# 3_MCU.net
KiCad netlist of a schematic drawn in Altium Designer
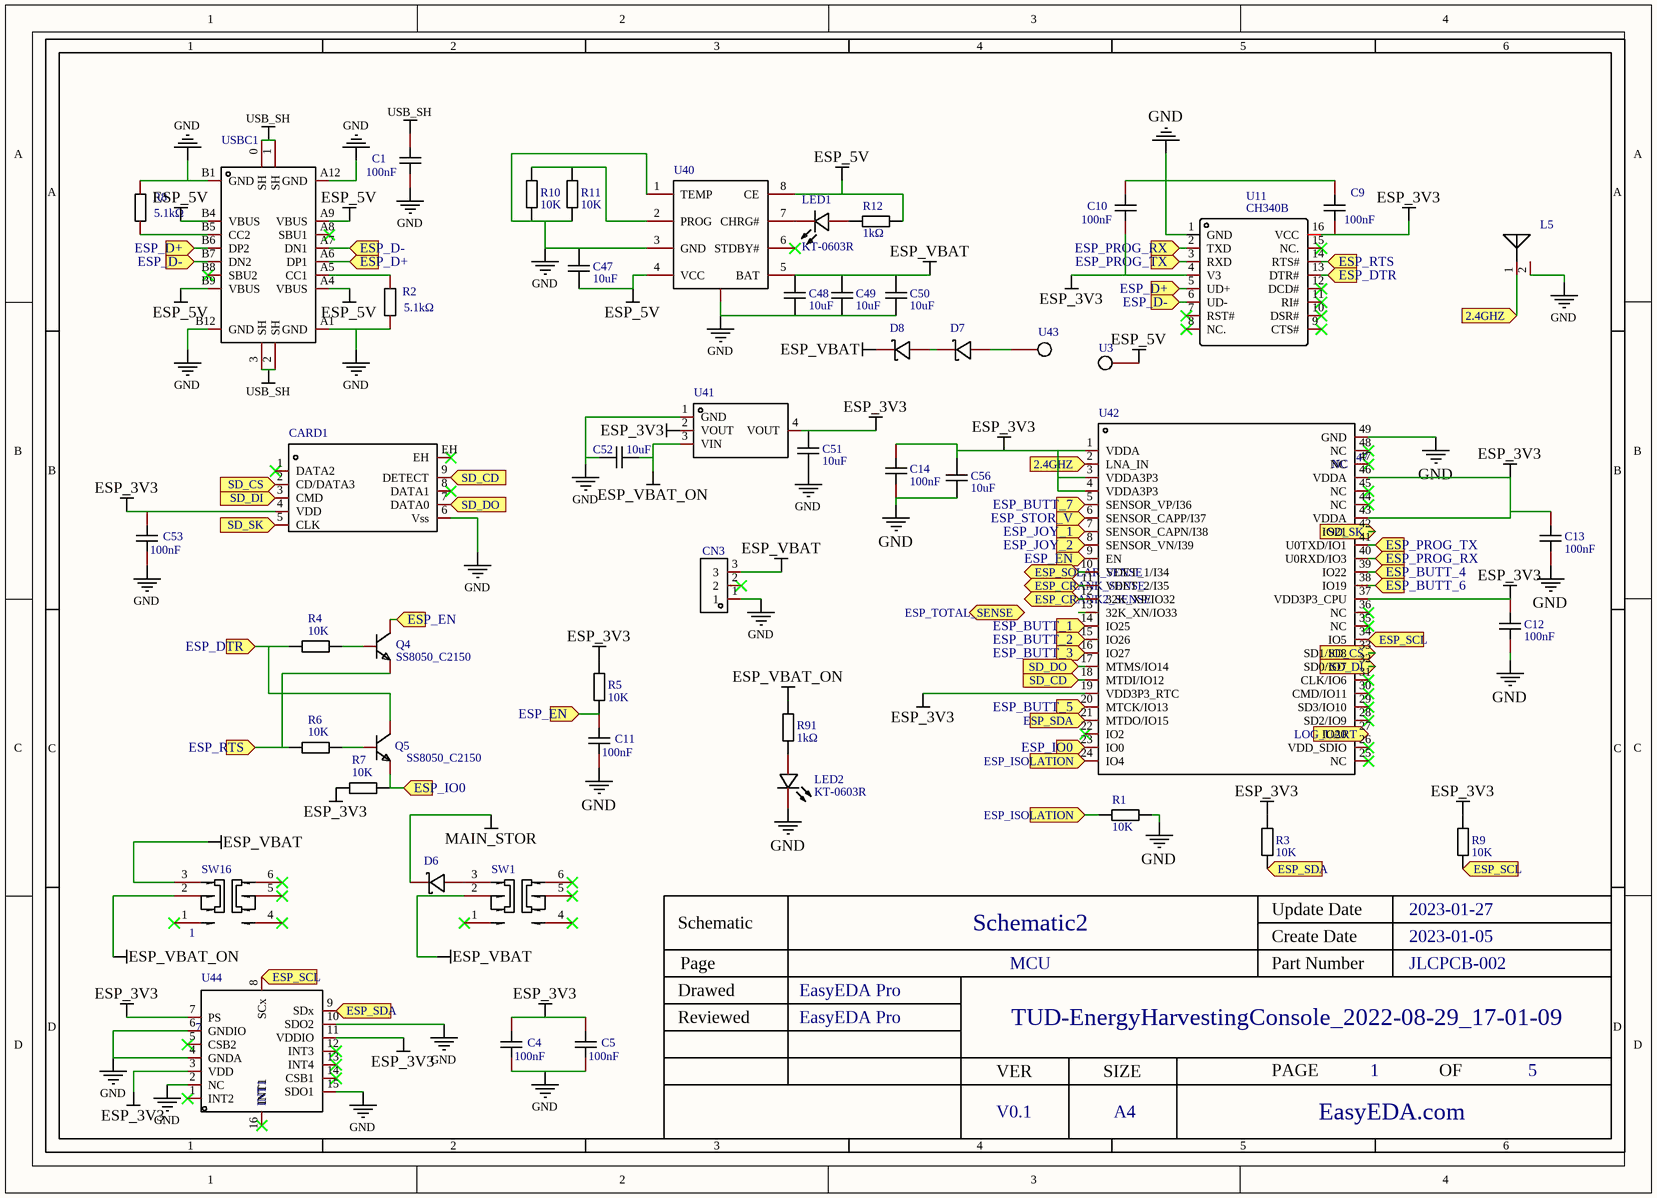
[diagram p0: 3_MCU.schdoc]

(export (version "E")
  (design (tool "Eeschema 10.0.6"))
  (components
    (comp (ref "C1")
      (value "100nF")
      (fields
        (field (name "NAME") "100nF")
        (field (name "MANUFACTURER") "YAGEO")
        (field (name "MANUFACTURER PART") "CC0603KRX7R9BB104")
      )
      (libsource (lib "altium-import") (part "root_1_CC0603KRX7R9BB104_"))
    )
    (comp (ref "C4")
      (value "100nF")
      (fields
        (field (name "NAME") "100nF")
        (field (name "MANUFACTURER") "YAGEO")
        (field (name "MANUFACTURER PART") "CC0603KRX7R9BB104")
      )
      (libsource (lib "altium-import") (part "root_1_CC0603KRX7R9BB104_"))
    )
    (comp (ref "C5")
      (value "100nF")
      (fields
        (field (name "NAME") "100nF")
        (field (name "MANUFACTURER") "YAGEO")
        (field (name "MANUFACTURER PART") "CC0603KRX7R9BB104")
      )
      (libsource (lib "altium-import") (part "root_1_CC0603KRX7R9BB104_"))
    )
    (comp (ref "C9")
      (value "100nF")
      (fields
        (field (name "NAME") "100nF")
        (field (name "MANUFACTURER") "YAGEO")
        (field (name "MANUFACTURER PART") "CC0603KRX7R9BB104")
      )
      (libsource (lib "altium-import") (part "root_1_CC0603KRX7R9BB104_"))
    )
    (comp (ref "C10")
      (value "100nF")
      (fields
        (field (name "NAME") "100nF")
        (field (name "MANUFACTURER") "YAGEO")
        (field (name "MANUFACTURER PART") "CC0603KRX7R9BB104")
      )
      (libsource (lib "altium-import") (part "root_1_CC0603KRX7R9BB104_"))
    )
    (comp (ref "C11")
      (value "100nF")
      (fields
        (field (name "NAME") "100nF")
        (field (name "MANUFACTURER") "YAGEO")
        (field (name "MANUFACTURER PART") "CC0603KRX7R9BB104")
      )
      (libsource (lib "altium-import") (part "root_1_CC0603KRX7R9BB104_"))
    )
    (comp (ref "C12")
      (value "100nF")
      (fields
        (field (name "NAME") "100nF")
        (field (name "MANUFACTURER PART") "CL05B104KO5NNNC")
        (field (name "MANUFACTURER") "SAMSUNG")
      )
      (libsource (lib "altium-import") (part "root_1_CL05B104KO5NNNC_"))
    )
    (comp (ref "C13")
      (value "100nF")
      (fields
        (field (name "NAME") "100nF")
        (field (name "MANUFACTURER PART") "CL05B104KO5NNNC")
        (field (name "MANUFACTURER") "SAMSUNG")
      )
      (libsource (lib "altium-import") (part "root_1_CL05B104KO5NNNC_"))
    )
    (comp (ref "C14")
      (value "100nF")
      (fields
        (field (name "NAME") "100nF")
        (field (name "MANUFACTURER PART") "CL05B104KO5NNNC")
        (field (name "MANUFACTURER") "SAMSUNG")
      )
      (libsource (lib "altium-import") (part "root_1_CL05B104KO5NNNC_"))
    )
    (comp (ref "C47")
      (value "10uF")
      (fields
        (field (name "NAME") "10uF")
        (field (name "MANUFACTURER PART") "CL05A106MQ5NUNC")
        (field (name "MANUFACTURER") "SAMSUNG")
      )
      (libsource (lib "altium-import") (part "root_3_CL05A106MQ5NUNC_"))
    )
    (comp (ref "C48")
      (value "10uF")
      (fields
        (field (name "NAME") "10uF")
        (field (name "MANUFACTURER PART") "CL05A106MQ5NUNC")
        (field (name "MANUFACTURER") "SAMSUNG")
      )
      (libsource (lib "altium-import") (part "root_3_CL05A106MQ5NUNC_"))
    )
    (comp (ref "C49")
      (value "10uF")
      (fields
        (field (name "NAME") "10uF")
        (field (name "MANUFACTURER PART") "CL05A106MQ5NUNC")
        (field (name "MANUFACTURER") "SAMSUNG")
      )
      (libsource (lib "altium-import") (part "root_3_CL05A106MQ5NUNC_"))
    )
    (comp (ref "C50")
      (value "10uF")
      (fields
        (field (name "NAME") "10uF")
        (field (name "MANUFACTURER PART") "CL05A106MQ5NUNC")
        (field (name "MANUFACTURER") "SAMSUNG")
      )
      (libsource (lib "altium-import") (part "root_3_CL05A106MQ5NUNC_"))
    )
    (comp (ref "C51")
      (value "10uF")
      (fields
        (field (name "NAME") "10uF")
        (field (name "MANUFACTURER PART") "CL05A106MQ5NUNC")
        (field (name "MANUFACTURER") "SAMSUNG")
      )
      (libsource (lib "altium-import") (part "root_3_CL05A106MQ5NUNC_"))
    )
    (comp (ref "C52")
      (value "10uF")
      (fields
        (field (name "NAME") "10uF")
        (field (name "MANUFACTURER PART") "CL05A106MQ5NUNC")
        (field (name "MANUFACTURER") "SAMSUNG")
      )
      (libsource (lib "altium-import") (part "root_0_CL05A106MQ5NUNC_"))
    )
    (comp (ref "C53")
      (value "100nF")
      (fields
        (field (name "NAME") "100nF")
        (field (name "MANUFACTURER") "YAGEO")
        (field (name "MANUFACTURER PART") "CC0603KRX7R9BB104")
      )
      (libsource (lib "altium-import") (part "root_1_CC0603KRX7R9BB104_"))
    )
    (comp (ref "C56")
      (value "10uF")
      (fields
        (field (name "NAME") "10uF")
        (field (name "MANUFACTURER PART") "CL05A106MQ5NUNC")
        (field (name "MANUFACTURER") "SAMSUNG")
      )
      (libsource (lib "altium-import") (part "root_3_CL05A106MQ5NUNC_"))
    )
    (comp (ref "CARD1")
      (value "473521001")
      (fields (field (name "MANUFACTURER") "MOLEX"))
      (libsource (lib "altium-import") (part "root_0_473521001_"))
    )
    (comp (ref "CN3")
      (value "X1502WR-03K-N0SN")
      (fields (field (name "MANUFACTURER") "XKB Connectivity(中国星坤)"))
      (libsource (lib "altium-import") (part "root_2_X1502WR-03K-N0SN_"))
    )
    (comp (ref "D6")
      (value "SS54")
      (description "Reverse Voltage (Vr):40V Average Rectified Current (Io):5A Forward Voltage (Vf@If):550mV@5A")
      (fields (field (name "MANUFACTURER") "MDD"))
      (libsource (lib "altium-import") (part "root_0_SS54_"))
    )
    (comp (ref "D7")
      (value "SS54")
      (description "Reverse Voltage (Vr):40V Average Rectified Current (Io):5A Forward Voltage (Vf@If):550mV@5A")
      (fields (field (name "MANUFACTURER") "MDD"))
      (libsource (lib "altium-import") (part "root_0_SS54_"))
    )
    (comp (ref "D8")
      (value "SS54")
      (description "Reverse Voltage (Vr):40V Average Rectified Current (Io):5A Forward Voltage (Vf@If):550mV@5A")
      (fields (field (name "MANUFACTURER") "MDD"))
      (libsource (lib "altium-import") (part "root_0_SS54_"))
    )
    (comp (ref "L5")
      (value "SLDA92-2R660G-S1TF")
      (fields (field (name "MANUFACTURER") "Sunlord(顺络)"))
      (libsource (lib "altium-import") (part "root_0_SLDA92-2R660G-S1TF_"))
    )
    (comp (ref "LED1")
      (value "KT-0603R")
      (fields (field (name "NAME") "KT-0603R") (field (name "MANUFACTURER") "KENTO"))
      (libsource (lib "altium-import") (part "root_0_KT-0603R_"))
    )
    (comp (ref "LED2")
      (value "KT-0603R")
      (fields (field (name "NAME") "KT-0603R") (field (name "MANUFACTURER") "KENTO"))
      (libsource (lib "altium-import") (part "root_1_KT-0603R_"))
    )
    (comp (ref "Q4")
      (value "SS8050_C2150")
      (fields
        (field (name "NAME") "SS8050_C2150")
        (field (name "MANUFACTURER") "CJ")
        (field (name "MANUFACTURER PART") "SS8050")
      )
      (libsource (lib "altium-import") (part "root_0_SS8050_"))
    )
    (comp (ref "Q5")
      (value "SS8050_C2150")
      (fields
        (field (name "NAME") "SS8050_C2150")
        (field (name "MANUFACTURER") "CJ")
        (field (name "MANUFACTURER PART") "SS8050")
      )
      (libsource (lib "altium-import") (part "root_0_SS8050_"))
    )
    (comp (ref "R1")
      (value "10K")
      (fields
        (field (name "NAME") "10K")
        (field (name "MANUFACTURER") "UniOhm")
        (field (name "MANUFACTURER PART") "0603WAF1002T5E")
      )
      (libsource (lib "altium-import") (part "root_2_0603WAF1002T5E_"))
    )
    (comp (ref "R2")
      (value "5.1kΩ")
      (fields
        (field (name "MANUFACTURER") "UNI-ROYAL(厚声)")
        (field (name "MANUFACTURER PART") "0603WAF5101T5E")
        (field (name "TOLERANCE") "±1%")
      )
      (libsource (lib "altium-import") (part "root_1_0603WAF5101T5E_"))
    )
    (comp (ref "R3")
      (value "10K")
      (fields
        (field (name "NAME") "10K")
        (field (name "MANUFACTURER") "UniOhm")
        (field (name "MANUFACTURER PART") "0603WAF1002T5E")
      )
      (libsource (lib "altium-import") (part "root_1_0603WAF1002T5E_"))
    )
    (comp (ref "R4")
      (value "10K")
      (fields
        (field (name "NAME") "10K")
        (field (name "MANUFACTURER") "UniOhm")
        (field (name "MANUFACTURER PART") "0603WAF1002T5E")
      )
      (libsource (lib "altium-import") (part "root_0_0603WAF1002T5E_"))
    )
    (comp (ref "R5")
      (value "10K")
      (fields
        (field (name "NAME") "10K")
        (field (name "MANUFACTURER") "UniOhm")
        (field (name "MANUFACTURER PART") "0603WAF1002T5E")
      )
      (libsource (lib "altium-import") (part "root_1_0603WAF1002T5E_"))
    )
    (comp (ref "R6")
      (value "10K")
      (fields
        (field (name "NAME") "10K")
        (field (name "MANUFACTURER") "UniOhm")
        (field (name "MANUFACTURER PART") "0603WAF1002T5E")
      )
      (libsource (lib "altium-import") (part "root_0_0603WAF1002T5E_"))
    )
    (comp (ref "R7")
      (value "10K")
      (fields
        (field (name "NAME") "10K")
        (field (name "MANUFACTURER") "UniOhm")
        (field (name "MANUFACTURER PART") "0603WAF1002T5E")
      )
      (libsource (lib "altium-import") (part "root_2_0603WAF1002T5E_"))
    )
    (comp (ref "R8")
      (value "5.1kΩ")
      (fields
        (field (name "MANUFACTURER") "UNI-ROYAL(厚声)")
        (field (name "MANUFACTURER PART") "0603WAF5101T5E")
        (field (name "TOLERANCE") "±1%")
      )
      (libsource (lib "altium-import") (part "root_1_0603WAF5101T5E_"))
    )
    (comp (ref "R9")
      (value "10K")
      (fields
        (field (name "NAME") "10K")
        (field (name "MANUFACTURER") "UniOhm")
        (field (name "MANUFACTURER PART") "0603WAF1002T5E")
      )
      (libsource (lib "altium-import") (part "root_1_0603WAF1002T5E_"))
    )
    (comp (ref "R10")
      (value "10K")
      (fields
        (field (name "NAME") "10K")
        (field (name "MANUFACTURER") "UniOhm")
        (field (name "MANUFACTURER PART") "0603WAF1002T5E")
      )
      (libsource (lib "altium-import") (part "root_1_0603WAF1002T5E_"))
    )
    (comp (ref "R11")
      (value "10K")
      (fields
        (field (name "NAME") "10K")
        (field (name "MANUFACTURER") "UniOhm")
        (field (name "MANUFACTURER PART") "0603WAF1002T5E")
      )
      (libsource (lib "altium-import") (part "root_1_0603WAF1002T5E_"))
    )
    (comp (ref "R12")
      (value "1kΩ")
      (fields
        (field (name "NAME") "1kΩ")
        (field (name "MANUFACTURER") "UniOhm")
        (field (name "MANUFACTURER PART") "0603WAF1001T5E")
      )
      (libsource (lib "altium-import") (part "root_0_0603WAF1001T5E_"))
    )
    (comp (ref "R91")
      (value "1kΩ")
      (fields
        (field (name "NAME") "1kΩ")
        (field (name "MANUFACTURER") "UniOhm")
        (field (name "MANUFACTURER PART") "0603WAF1001T5E")
      )
      (libsource (lib "altium-import") (part "root_1_0603WAF1001T5E_"))
    )
    (comp (ref "SW1")
      (value "SS-3235S-L1")
      (fields (field (name "MANUFACTURER") "XKB Connectivity(中国星坤)"))
      (libsource (lib "altium-import") (part "root_1_SS-3235S-L1_"))
    )
    (comp (ref "SW16")
      (value "SS-3235S-L1")
      (fields (field (name "MANUFACTURER") "XKB Connectivity(中国星坤)") (field (name "NUMBER") "1"))
      (libsource (lib "altium-import") (part "root_1_SS-3235S-L1_"))
    )
    (comp (ref "U3") (value "SMD_PAD") (libsource (lib "altium-import") (part "root_2_SMD_PAD_")))
    (comp (ref "U11")
      (value "CH340B")
      (fields (field (name "NAME") "CH340B") (field (name "MANUFACTURER") "WCH"))
      (libsource (lib "altium-import") (part "root_0_CH340B_"))
    )
    (comp (ref "U40")
      (value "TP4056M")
      (fields (field (name "MANUFACTURER") "TOPPOWER(南京拓微)"))
      (libsource (lib "altium-import") (part "root_0_TP4056M_"))
    )
    (comp (ref "U41")
      (value "AMS1117-3.3")
      (fields (field (name "MANUFACTURER") "美国AMS"))
      (libsource (lib "altium-import") (part "root_0_AMS1117-3.3_"))
    )
    (comp (ref "U42")
      (value "ESP32-PICO-V3")
      (fields
        (field (name "MANUFACTURER") "ESPRESSIF(乐鑫)")
        (field (name "NAME") "NC")
        (field (name "NUMBER") "47")
      )
      (libsource (lib "altium-import") (part "root_0_ESP32-PICO-V3_"))
    )
    (comp (ref "U43") (value "SMD_PAD") (libsource (lib "altium-import") (part "root_0_SMD_PAD_")))
    (comp (ref "U44")
      (value "BMI055")
      (fields
        (field (name "MANUFACTURER") "Bosch(博世)")
        (field (name "NAME") "INT1")
        (field (name "NUMBER") "7")
      )
      (libsource (lib "altium-import") (part "root_1_BMI055_"))
    )
    (comp (ref "USBC1")
      (value "TYPE-C-31-M-12")
      (fields (field (name "MANUFACTURER") "韩国韩荣"))
      (libsource (lib "altium-import") (part "root_0_TYPE-C-31-M-12_"))
    )
  )
  (nets
    (net (code "1") (name "/2.4GHZ") (class "Default")
      (node (ref "L5") (pin "1") (pinfunction "1_1") (pintype "passive"))
      (node (ref "U42") (pin "2") (pinfunction "LNA_IN_2") (pintype "passive"))
    )
    (net (code "2") (name "/ESP_BUTT_1") (class "Default")
      (node (ref "U42") (pin "14") (pinfunction "IO25_14") (pintype "passive"))
    )
    (net (code "3") (name "/ESP_BUTT_2") (class "Default")
      (node (ref "U42") (pin "15") (pinfunction "IO26_15") (pintype "passive"))
    )
    (net (code "4") (name "/ESP_BUTT_3") (class "Default")
      (node (ref "U42") (pin "16") (pinfunction "IO27_16") (pintype "passive"))
    )
    (net (code "5") (name "/ESP_BUTT_4") (class "Default")
      (node (ref "U42") (pin "39") (pinfunction "IO22_39") (pintype "passive"))
    )
    (net (code "6") (name "/ESP_BUTT_5") (class "Default")
      (node (ref "U42") (pin "20") (pinfunction "MTCK/IO13_20") (pintype "passive"))
    )
    (net (code "7") (name "/ESP_BUTT_6") (class "Default")
      (node (ref "U42") (pin "38") (pinfunction "IO19_38") (pintype "passive"))
    )
    (net (code "8") (name "/ESP_BUTT_7") (class "Default")
      (node (ref "U42") (pin "5") (pinfunction "SENSOR_VP/I36_5") (pintype "passive"))
    )
    (net (code "9") (name "/ESP_CRANK2_SENSE") (class "Default")
      (node (ref "U42") (pin "12") (pinfunction "32K_XP/IO32_12") (pintype "passive"))
    )
    (net (code "10") (name "/ESP_CRANK_SENSE") (class "Default")
      (node (ref "U42") (pin "11") (pinfunction "VDET_2/I35_11") (pintype "passive"))
    )
    (net (code "11") (name "/ESP_D+") (class "Default")
      (node (ref "U11") (pin "5") (pinfunction "UD+_5") (pintype "passive"))
      (node (ref "USBC1") (pin "A6") (pinfunction "DP1_A6") (pintype "passive"))
      (node (ref "USBC1") (pin "B6") (pinfunction "DP2_B6") (pintype "passive"))
    )
    (net (code "12") (name "/ESP_D-") (class "Default")
      (node (ref "U11") (pin "6") (pinfunction "UD-_6") (pintype "passive"))
      (node (ref "USBC1") (pin "A7") (pinfunction "DN1_A7") (pintype "passive"))
      (node (ref "USBC1") (pin "B7") (pinfunction "DN2_B7") (pintype "passive"))
    )
    (net (code "13") (name "/ESP_DTR") (class "Default")
      (node (ref "Q5") (pin "3") (pinfunction "C_3") (pintype "passive"))
      (node (ref "R4") (pin "1") (pinfunction "1_1") (pintype "passive"))
      (node (ref "U11") (pin "13") (pinfunction "DTR#_13") (pintype "passive"))
    )
    (net (code "14") (name "/ESP_EN") (class "Default")
      (node (ref "C11") (pin "2") (pinfunction "2_2") (pintype "passive"))
      (node (ref "Q4") (pin "3") (pinfunction "C_3") (pintype "passive"))
      (node (ref "R5") (pin "1") (pinfunction "1_1") (pintype "passive"))
      (node (ref "U42") (pin "9") (pinfunction "EN_9") (pintype "passive"))
    )
    (net (code "15") (name "/ESP_IO0") (class "Default")
      (node (ref "Q5") (pin "2") (pinfunction "E_2") (pintype "passive"))
      (node (ref "R7") (pin "1") (pinfunction "1_1") (pintype "passive"))
      (node (ref "U42") (pin "23") (pinfunction "IO0_23") (pintype "passive"))
    )
    (net (code "16") (name "/ESP_ISOLATION") (class "Default")
      (node (ref "R1") (pin "2") (pinfunction "2_2") (pintype "passive"))
      (node (ref "U42") (pin "24") (pinfunction "IO4_24") (pintype "passive"))
    )
    (net (code "17") (name "/ESP_JOY_1") (class "Default")
      (node (ref "U42") (pin "7") (pinfunction "SENSOR_CAPN/I38_7") (pintype "passive"))
    )
    (net (code "18") (name "/ESP_JOY_2") (class "Default")
      (node (ref "U42") (pin "8") (pinfunction "SENSOR_VN/I39_8") (pintype "passive"))
    )
    (net (code "19") (name "/ESP_PROG_RX") (class "Default")
      (node (ref "U11") (pin "2") (pinfunction "TXD_2") (pintype "passive"))
      (node (ref "U42") (pin "40") (pinfunction "U0RXD/IO3_40") (pintype "passive"))
    )
    (net (code "20") (name "/ESP_PROG_TX") (class "Default")
      (node (ref "U11") (pin "3") (pinfunction "RXD_3") (pintype "passive"))
      (node (ref "U42") (pin "41") (pinfunction "U0TXD/IO1_41") (pintype "passive"))
    )
    (net (code "21") (name "/ESP_RTS") (class "Default")
      (node (ref "Q4") (pin "2") (pinfunction "E_2") (pintype "passive"))
      (node (ref "R6") (pin "1") (pinfunction "1_1") (pintype "passive"))
      (node (ref "U11") (pin "14") (pinfunction "RTS#_14") (pintype "passive"))
    )
    (net (code "22") (name "/ESP_SCL") (class "Default")
      (node (ref "R9") (pin "1") (pinfunction "1_1") (pintype "passive"))
      (node (ref "U42") (pin "34") (pinfunction "IO5_34") (pintype "passive"))
      (node (ref "U44") (pin "8") (pinfunction "SCx_8") (pintype "passive"))
    )
    (net (code "23") (name "/ESP_SDA") (class "Default")
      (node (ref "R3") (pin "1") (pinfunction "1_1") (pintype "passive"))
      (node (ref "U42") (pin "21") (pinfunction "MTDO/IO15_21") (pintype "passive"))
      (node (ref "U44") (pin "9") (pinfunction "SDx_9") (pintype "passive"))
    )
    (net (code "24") (name "/ESP_SOLAR_SENSE") (class "Default")
      (node (ref "U42") (pin "10") (pinfunction "VDET_1/I34_10") (pintype "passive"))
    )
    (net (code "25") (name "/ESP_STOR_V") (class "Default")
      (node (ref "U42") (pin "6") (pinfunction "SENSOR_CAPP/I37_6") (pintype "passive"))
    )
    (net (code "27") (name "/LOG_UART") (class "Default")
      (node (ref "U42") (pin "27") (pinfunction "IO20_27") (pintype "passive"))
    )
    (net (code "28") (name "/SD_CD") (class "Default")
      (node (ref "CARD1") (pin "9") (pinfunction "DETECT_9") (pintype "passive"))
      (node (ref "U42") (pin "18") (pinfunction "MTDI/IO12_18") (pintype "passive"))
    )
    (net (code "29") (name "/SD_CS") (class "Default")
      (node (ref "CARD1") (pin "2") (pinfunction "CD/DATA3_2") (pintype "passive"))
      (node (ref "U42") (pin "33") (pinfunction "SD1/IO8_33") (pintype "passive"))
    )
    (net (code "30") (name "/SD_DI") (class "Default")
      (node (ref "CARD1") (pin "3") (pinfunction "CMD_3") (pintype "passive"))
      (node (ref "U42") (pin "32") (pinfunction "SD0/IO7_32") (pintype "passive"))
    )
    (net (code "31") (name "/SD_DO") (class "Default")
      (node (ref "CARD1") (pin "7") (pinfunction "DATA0_7") (pintype "passive"))
      (node (ref "U42") (pin "17") (pinfunction "MTMS/IO14_17") (pintype "passive"))
    )
    (net (code "32") (name "/SD_SK") (class "Default")
      (node (ref "CARD1") (pin "5") (pinfunction "CLK_5") (pintype "passive"))
      (node (ref "U42") (pin "42") (pinfunction "IO21_42") (pintype "passive"))
    )
    (net (code "33") (name "ESP_3V3") (class "Default")
      (node (ref "C10") (pin "1") (pinfunction "1_1") (pintype "passive"))
      (node (ref "C12") (pin "2") (pinfunction "2_2") (pintype "passive"))
      (node (ref "C13") (pin "2") (pinfunction "2_2") (pintype "passive"))
      (node (ref "C14") (pin "2") (pinfunction "2_2") (pintype "passive"))
      (node (ref "C4") (pin "2") (pinfunction "2_2") (pintype "passive"))
      (node (ref "C5") (pin "2") (pinfunction "2_2") (pintype "passive"))
      (node (ref "C51") (pin "1") (pinfunction "1_1") (pintype "passive"))
      (node (ref "C53") (pin "2") (pinfunction "2_2") (pintype "passive"))
      (node (ref "C56") (pin "1") (pinfunction "1_1") (pintype "passive"))
      (node (ref "C9") (pin "1") (pinfunction "1_1") (pintype "passive"))
      (node (ref "CARD1") (pin "4") (pinfunction "VDD_4") (pintype "passive"))
      (node (ref "R3") (pin "2") (pinfunction "2_2") (pintype "passive"))
      (node (ref "R5") (pin "2") (pinfunction "2_2") (pintype "passive"))
      (node (ref "R7") (pin "2") (pinfunction "2_2") (pintype "passive"))
      (node (ref "R9") (pin "2") (pinfunction "2_2") (pintype "passive"))
      (node (ref "U11") (pin "16") (pinfunction "VCC_16") (pintype "passive"))
      (node (ref "U11") (pin "4") (pinfunction "V3_4") (pintype "passive"))
      (node (ref "U41") (pin "2") (pinfunction "VOUT_2") (pintype "passive"))
      (node (ref "U41") (pin "4") (pinfunction "VOUT_4") (pintype "passive"))
      (node (ref "U42") (pin "1") (pinfunction "VDDA_1") (pintype "passive"))
      (node (ref "U42") (pin "19") (pinfunction "VDD3P3_RTC_19") (pintype "passive"))
      (node (ref "U42") (pin "3") (pinfunction "VDDA3P3_3") (pintype "passive"))
      (node (ref "U42") (pin "37") (pinfunction "VDD3P3_CPU_37") (pintype "passive"))
      (node (ref "U42") (pin "4") (pinfunction "VDDA3P3_4") (pintype "passive"))
      (node (ref "U42") (pin "43") (pinfunction "VDDA_43") (pintype "passive"))
      (node (ref "U42") (pin "46") (pinfunction "VDDA_46") (pintype "passive"))
      (node (ref "U44") (pin "11") (pinfunction "VDDIO_11") (pintype "passive"))
      (node (ref "U44") (pin "3") (pinfunction "VDD_3") (pintype "passive"))
      (node (ref "U44") (pin "7") (pinfunction "PS_7") (pintype "passive"))
    )
    (net (code "34") (name "ESP_5V") (class "Default")
      (node (ref "C47") (pin "2") (pinfunction "2_2") (pintype "passive"))
      (node (ref "R12") (pin "2") (pinfunction "2_2") (pintype "passive"))
      (node (ref "U3") (pin "1") (pinfunction "1_1") (pintype "passive"))
      (node (ref "U40") (pin "4") (pinfunction "VCC_4") (pintype "passive"))
      (node (ref "U40") (pin "8") (pinfunction "CE_8") (pintype "passive"))
      (node (ref "USBC1") (pin "A4") (pinfunction "VBUS_A4") (pintype "passive"))
      (node (ref "USBC1") (pin "A9") (pinfunction "VBUS_A9") (pintype "passive"))
      (node (ref "USBC1") (pin "B4") (pinfunction "VBUS_B4") (pintype "passive"))
      (node (ref "USBC1") (pin "B9") (pinfunction "VBUS_B9") (pintype "passive"))
    )
    (net (code "35") (name "ESP_VBAT") (class "Default")
      (node (ref "C48") (pin "1") (pinfunction "1_1") (pintype "passive"))
      (node (ref "C49") (pin "1") (pinfunction "1_1") (pintype "passive"))
      (node (ref "C50") (pin "1") (pinfunction "1_1") (pintype "passive"))
      (node (ref "CN3") (pin "3") (pinfunction "3_3") (pintype "passive"))
      (node (ref "D8") (pin "2") (pinfunction "K_2") (pintype "passive"))
      (node (ref "SW1") (pin "2") (pinfunction "2_2") (pintype "passive"))
      (node (ref "SW16") (pin "3") (pinfunction "3_3") (pintype "passive"))
      (node (ref "U40") (pin "5") (pinfunction "BAT_5") (pintype "passive"))
    )
    (net (code "36") (name "ESP_VBAT_ON") (class "Default")
      (node (ref "C52") (pin "2") (pinfunction "2_2") (pintype "passive"))
      (node (ref "R91") (pin "2") (pinfunction "2_2") (pintype "passive"))
      (node (ref "SW16") (pin "2") (pinfunction "2_2") (pintype "passive"))
      (node (ref "U41") (pin "3") (pinfunction "VIN_3") (pintype "passive"))
    )
    (net (code "37") (name "GND") (class "Default")
      (node (ref "C1") (pin "1") (pinfunction "1_1") (pintype "passive"))
      (node (ref "C10") (pin "2") (pinfunction "2_2") (pintype "passive"))
      (node (ref "C11") (pin "1") (pinfunction "1_1") (pintype "passive"))
      (node (ref "C12") (pin "1") (pinfunction "1_1") (pintype "passive"))
      (node (ref "C13") (pin "1") (pinfunction "1_1") (pintype "passive"))
      (node (ref "C14") (pin "1") (pinfunction "1_1") (pintype "passive"))
      (node (ref "C4") (pin "1") (pinfunction "1_1") (pintype "passive"))
      (node (ref "C47") (pin "1") (pinfunction "1_1") (pintype "passive"))
      (node (ref "C48") (pin "2") (pinfunction "2_2") (pintype "passive"))
      (node (ref "C49") (pin "2") (pinfunction "2_2") (pintype "passive"))
      (node (ref "C5") (pin "1") (pinfunction "1_1") (pintype "passive"))
      (node (ref "C50") (pin "2") (pinfunction "2_2") (pintype "passive"))
      (node (ref "C51") (pin "2") (pinfunction "2_2") (pintype "passive"))
      (node (ref "C52") (pin "1") (pinfunction "1_1") (pintype "passive"))
      (node (ref "C53") (pin "1") (pinfunction "1_1") (pintype "passive"))
      (node (ref "C56") (pin "2") (pinfunction "2_2") (pintype "passive"))
      (node (ref "C9") (pin "2") (pinfunction "2_2") (pintype "passive"))
      (node (ref "CARD1") (pin "6") (pinfunction "Vss_6") (pintype "passive"))
      (node (ref "CN3") (pin "1") (pinfunction "1_1") (pintype "passive"))
      (node (ref "L5") (pin "2") (pinfunction "NC_2") (pintype "passive"))
      (node (ref "LED2") (pin "2") (pinfunction "K_2") (pintype "passive"))
      (node (ref "R1") (pin "1") (pinfunction "1_1") (pintype "passive"))
      (node (ref "R10") (pin "1") (pinfunction "1_1") (pintype "passive"))
      (node (ref "R11") (pin "1") (pinfunction "1_1") (pintype "passive"))
      (node (ref "R2") (pin "1") (pinfunction "1_1") (pintype "passive"))
      (node (ref "R8") (pin "2") (pinfunction "2_2") (pintype "passive"))
      (node (ref "U11") (pin "1") (pinfunction "GND_1") (pintype "passive"))
      (node (ref "U40") (pin "1") (pinfunction "TEMP_1") (pintype "passive"))
      (node (ref "U40") (pin "3") (pinfunction "GND_3") (pintype "passive"))
      (node (ref "U40") (pin "9") (pinfunction "9_9") (pintype "passive"))
      (node (ref "U41") (pin "1") (pinfunction "GND_1") (pintype "passive"))
      (node (ref "U42") (pin "49") (pinfunction "GND_49") (pintype "passive"))
      (node (ref "U44") (pin "10") (pinfunction "SDO2_10") (pintype "passive"))
      (node (ref "U44") (pin "15") (pinfunction "SDO1_15") (pintype "passive"))
      (node (ref "U44") (pin "2") (pinfunction "NC_2") (pintype "passive"))
      (node (ref "U44") (pin "4") (pinfunction "GNDA_4") (pintype "passive"))
      (node (ref "U44") (pin "6") (pinfunction "GNDIO_6") (pintype "passive"))
      (node (ref "USBC1") (pin "A1") (pinfunction "GND_A1") (pintype "passive"))
      (node (ref "USBC1") (pin "A12") (pinfunction "GND_A12") (pintype "passive"))
      (node (ref "USBC1") (pin "B1") (pinfunction "GND_B1") (pintype "passive"))
      (node (ref "USBC1") (pin "B12") (pinfunction "GND_B12") (pintype "passive"))
    )
    (net (code "38") (name "MAIN_STOR") (class "Default")
      (node (ref "D6") (pin "2") (pinfunction "K_2") (pintype "passive"))
    )
    (net (code "39") (name "Net-(D6-A)") (class "Default")
      (node (ref "D6") (pin "1") (pinfunction "A_1") (pintype "passive"))
      (node (ref "SW1") (pin "3") (pinfunction "3_3") (pintype "passive"))
    )
    (net (code "40") (name "Net-(D7-A)") (class "Default")
      (node (ref "D7") (pin "1") (pinfunction "A_1") (pintype "passive"))
      (node (ref "U43") (pin "1") (pinfunction "1_1") (pintype "passive"))
    )
    (net (code "41") (name "Net-(D7-K)") (class "Default")
      (node (ref "D7") (pin "2") (pinfunction "K_2") (pintype "passive"))
      (node (ref "D8") (pin "1") (pinfunction "A_1") (pintype "passive"))
    )
    (net (code "42") (name "Net-(LED1-A)") (class "Default")
      (node (ref "LED1") (pin "1") (pinfunction "A_1") (pintype "passive"))
      (node (ref "R12") (pin "1") (pinfunction "1_1") (pintype "passive"))
    )
    (net (code "43") (name "Net-(LED1-K)") (class "Default")
      (node (ref "LED1") (pin "2") (pinfunction "K_2") (pintype "passive"))
      (node (ref "U40") (pin "7") (pinfunction "CHRG#_7") (pintype "passive"))
    )
    (net (code "44") (name "Net-(LED2-A)") (class "Default")
      (node (ref "LED2") (pin "1") (pinfunction "A_1") (pintype "passive"))
      (node (ref "R91") (pin "1") (pinfunction "1_1") (pintype "passive"))
    )
    (net (code "45") (name "Net-(Q4-B)") (class "Default")
      (node (ref "Q4") (pin "1") (pinfunction "B_1") (pintype "passive"))
      (node (ref "R4") (pin "2") (pinfunction "2_2") (pintype "passive"))
    )
    (net (code "46") (name "Net-(Q5-B)") (class "Default")
      (node (ref "Q5") (pin "1") (pinfunction "B_1") (pintype "passive"))
      (node (ref "R6") (pin "2") (pinfunction "2_2") (pintype "passive"))
    )
    (net (code "47") (name "Net-(U40-PROG)") (class "Default")
      (node (ref "R10") (pin "2") (pinfunction "2_2") (pintype "passive"))
      (node (ref "R11") (pin "2") (pinfunction "2_2") (pintype "passive"))
      (node (ref "U40") (pin "2") (pinfunction "PROG_2") (pintype "passive"))
    )
    (net (code "48") (name "Net-(USBC1-CC1)") (class "Default")
      (node (ref "R2") (pin "2") (pinfunction "2_2") (pintype "passive"))
      (node (ref "USBC1") (pin "A5") (pinfunction "CC1_A5") (pintype "passive"))
    )
    (net (code "49") (name "Net-(USBC1-CC2)") (class "Default")
      (node (ref "R8") (pin "1") (pinfunction "1_1") (pintype "passive"))
      (node (ref "USBC1") (pin "B5") (pinfunction "CC2_B5") (pintype "passive"))
    )
    (net (code "50") (name "USB_SH") (class "Default")
      (node (ref "C1") (pin "2") (pinfunction "2_2") (pintype "passive"))
      (node (ref "USBC1") (pin "0") (pinfunction "SH_0") (pintype "passive"))
      (node (ref "USBC1") (pin "1") (pinfunction "SH_1") (pintype "passive"))
      (node (ref "USBC1") (pin "2") (pinfunction "SH_2") (pintype "passive"))
      (node (ref "USBC1") (pin "3") (pinfunction "SH_3") (pintype "passive"))
    )
    (net (code "51") (name "unconnected-(CARD1-DATA1-Pad8)") (class "Default")
      (node (ref "CARD1") (pin "8") (pinfunction "DATA1_8") (pintype "passive+no_connect"))
    )
    (net (code "52") (name "unconnected-(CARD1-DATA2-Pad1)") (class "Default")
      (node (ref "CARD1") (pin "1") (pinfunction "DATA2_1") (pintype "passive+no_connect"))
    )
    (net (code "53") (name "unconnected-(CARD1-PadEH)") (class "Default")
      (node (ref "CARD1") (pin "EH") (pinfunction "EH_EH") (pintype "passive+no_connect"))
    )
    (net (code "54") (name "unconnected-(CN3-Pad2)") (class "Default")
      (node (ref "CN3") (pin "2") (pinfunction "2_2") (pintype "passive+no_connect"))
    )
    (net (code "55") (name "unconnected-(SW1-Pad1)") (class "Default")
      (node (ref "SW1") (pin "1") (pinfunction "1_1") (pintype "passive+no_connect"))
    )
    (net (code "56") (name "unconnected-(SW1-Pad4)") (class "Default")
      (node (ref "SW1") (pin "4") (pinfunction "4_4") (pintype "passive+no_connect"))
    )
    (net (code "57") (name "unconnected-(SW1-Pad5)") (class "Default")
      (node (ref "SW1") (pin "5") (pinfunction "5_5") (pintype "passive+no_connect"))
    )
    (net (code "58") (name "unconnected-(SW1-Pad6)") (class "Default")
      (node (ref "SW1") (pin "6") (pinfunction "6_6") (pintype "passive+no_connect"))
    )
    (net (code "59") (name "unconnected-(SW16-Pad1)") (class "Default")
      (node (ref "SW16") (pin "1") (pinfunction "1_1") (pintype "passive+no_connect"))
    )
    (net (code "60") (name "unconnected-(SW16-Pad4)") (class "Default")
      (node (ref "SW16") (pin "4") (pinfunction "4_4") (pintype "passive+no_connect"))
    )
    (net (code "61") (name "unconnected-(SW16-Pad5)") (class "Default")
      (node (ref "SW16") (pin "5") (pinfunction "5_5") (pintype "passive+no_connect"))
    )
    (net (code "62") (name "unconnected-(SW16-Pad6)") (class "Default")
      (node (ref "SW16") (pin "6") (pinfunction "6_6") (pintype "passive+no_connect"))
    )
    (net (code "63") (name "unconnected-(U11-CTS#-Pad9)") (class "Default")
      (node (ref "U11") (pin "9") (pinfunction "CTS#_9") (pintype "passive+no_connect"))
    )
    (net (code "64") (name "unconnected-(U11-DCD#-Pad12)") (class "Default")
      (node (ref "U11") (pin "12") (pinfunction "DCD#_12") (pintype "passive+no_connect"))
    )
    (net (code "65") (name "unconnected-(U11-DSR#-Pad10)") (class "Default")
      (node (ref "U11") (pin "10") (pinfunction "DSR#_10") (pintype "passive+no_connect"))
    )
    (net (code "66") (name "unconnected-(U11-NC.-Pad8)") (class "Default")
      (node (ref "U11") (pin "8") (pinfunction "NC._8") (pintype "passive+no_connect"))
    )
    (net (code "67") (name "unconnected-(U11-NC.-Pad15)") (class "Default")
      (node (ref "U11") (pin "15") (pinfunction "NC._15") (pintype "passive+no_connect"))
    )
    (net (code "68") (name "unconnected-(U11-RI#-Pad11)") (class "Default")
      (node (ref "U11") (pin "11") (pinfunction "RI#_11") (pintype "passive+no_connect"))
    )
    (net (code "69") (name "unconnected-(U11-RST#-Pad7)") (class "Default")
      (node (ref "U11") (pin "7") (pinfunction "RST#_7") (pintype "passive+no_connect"))
    )
    (net (code "70") (name "unconnected-(U40-STDBY#-Pad6)") (class "Default")
      (node (ref "U40") (pin "6") (pinfunction "STDBY#_6") (pintype "passive+no_connect"))
    )
    (net (code "71") (name "unconnected-(U42-32K_XN{slash}IO33-Pad13)") (class "Default")
      (node (ref "U42") (pin "13") (pinfunction "32K_XN/IO33_13") (pintype "passive"))
    )
    (net (code "72") (name "unconnected-(U42-CLK{slash}IO6-Pad31)") (class "Default")
      (node (ref "U42") (pin "31") (pinfunction "CLK/IO6_31") (pintype "passive+no_connect"))
    )
    (net (code "73") (name "unconnected-(U42-CMD{slash}IO11-Pad30)") (class "Default")
      (node (ref "U42") (pin "30") (pinfunction "CMD/IO11_30") (pintype "passive+no_connect"))
    )
    (net (code "74") (name "unconnected-(U42-IO2-Pad22)") (class "Default")
      (node (ref "U42") (pin "22") (pinfunction "IO2_22") (pintype "passive+no_connect"))
    )
    (net (code "75") (name "unconnected-(U42-NC-Pad25)") (class "Default")
      (node (ref "U42") (pin "25") (pinfunction "NC_25") (pintype "passive+no_connect"))
    )
    (net (code "76") (name "unconnected-(U42-NC-Pad35)") (class "Default")
      (node (ref "U42") (pin "35") (pinfunction "NC_35") (pintype "passive+no_connect"))
    )
    (net (code "77") (name "unconnected-(U42-NC-Pad36)") (class "Default")
      (node (ref "U42") (pin "36") (pinfunction "NC_36") (pintype "passive+no_connect"))
    )
    (net (code "78") (name "unconnected-(U42-NC-Pad44)") (class "Default")
      (node (ref "U42") (pin "44") (pinfunction "NC_44") (pintype "passive+no_connect"))
    )
    (net (code "79") (name "unconnected-(U42-NC-Pad45)") (class "Default")
      (node (ref "U42") (pin "45") (pinfunction "NC_45") (pintype "passive+no_connect"))
    )
    (net (code "80") (name "unconnected-(U42-NC-Pad47)") (class "Default")
      (node (ref "U42") (pin "47") (pinfunction "NC_47") (pintype "passive+no_connect"))
    )
    (net (code "81") (name "unconnected-(U42-NC-Pad48)") (class "Default")
      (node (ref "U42") (pin "48") (pinfunction "NC_48") (pintype "passive+no_connect"))
    )
    (net (code "82") (name "unconnected-(U42-SD2{slash}IO9-Pad28)") (class "Default")
      (node (ref "U42") (pin "28") (pinfunction "SD2/IO9_28") (pintype "passive+no_connect"))
    )
    (net (code "83") (name "unconnected-(U42-SD3{slash}IO10-Pad29)") (class "Default")
      (node (ref "U42") (pin "29") (pinfunction "SD3/IO10_29") (pintype "passive+no_connect"))
    )
    (net (code "84") (name "unconnected-(U42-VDD_SDIO-Pad26)") (class "Default")
      (node (ref "U42") (pin "26") (pinfunction "VDD_SDIO_26") (pintype "passive+no_connect"))
    )
    (net (code "85") (name "unconnected-(U44-CSB1-Pad14)") (class "Default")
      (node (ref "U44") (pin "14") (pinfunction "CSB1_14") (pintype "passive+no_connect"))
    )
    (net (code "86") (name "unconnected-(U44-CSB2-Pad5)") (class "Default")
      (node (ref "U44") (pin "5") (pinfunction "CSB2_5") (pintype "passive+no_connect"))
    )
    (net (code "87") (name "unconnected-(U44-INT1-Pad16)") (class "Default")
      (node (ref "U44") (pin "16") (pinfunction "INT1_16") (pintype "passive+no_connect"))
    )
    (net (code "88") (name "unconnected-(U44-INT2-Pad1)") (class "Default")
      (node (ref "U44") (pin "1") (pinfunction "INT2_1") (pintype "passive+no_connect"))
    )
    (net (code "89") (name "unconnected-(U44-INT3-Pad12)") (class "Default")
      (node (ref "U44") (pin "12") (pinfunction "INT3_12") (pintype "passive+no_connect"))
    )
    (net (code "90") (name "unconnected-(U44-INT4-Pad13)") (class "Default")
      (node (ref "U44") (pin "13") (pinfunction "INT4_13") (pintype "passive+no_connect"))
    )
    (net (code "91") (name "unconnected-(USBC1-SBU1-PadA8)") (class "Default")
      (node (ref "USBC1") (pin "A8") (pinfunction "SBU1_A8") (pintype "passive+no_connect"))
    )
    (net (code "92") (name "unconnected-(USBC1-SBU2-PadB8)") (class "Default")
      (node (ref "USBC1") (pin "B8") (pinfunction "SBU2_B8") (pintype "passive+no_connect"))
    )
  )
)
